# 3_6_1--esp32_-_7-2.net
KiCad netlist of a schematic drawn in EasyEDA Pro
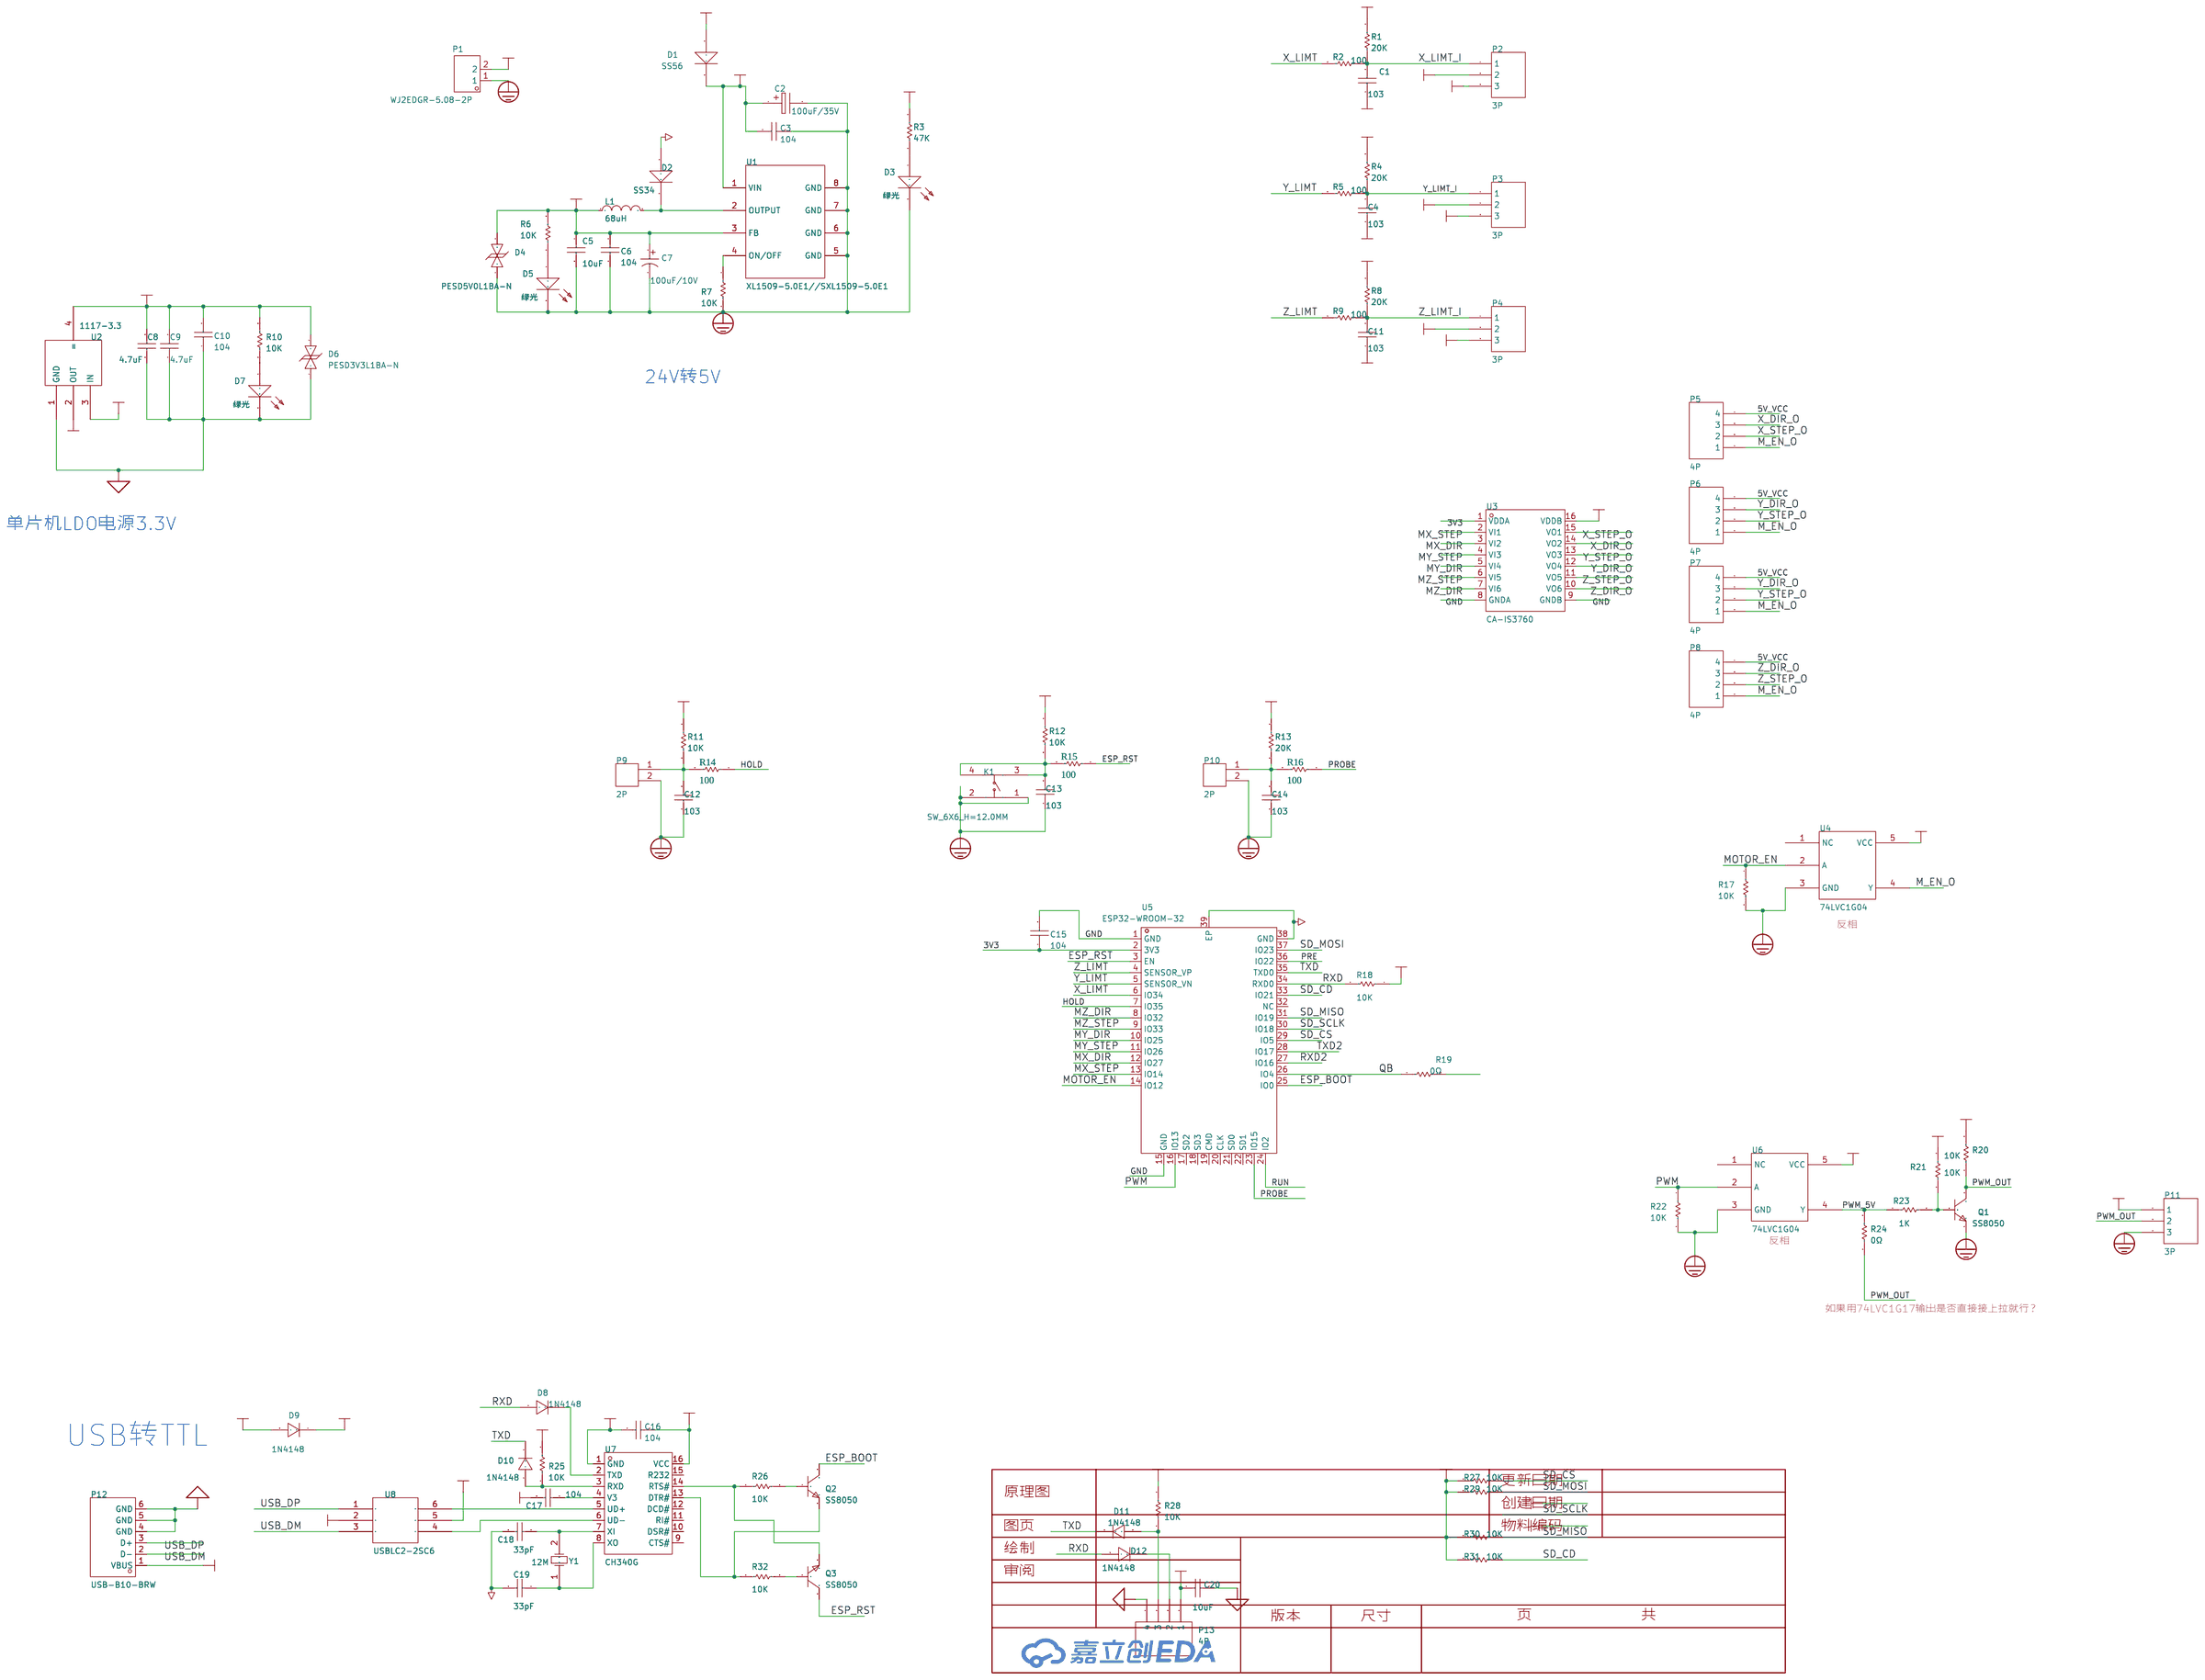
[diagram p0: schematic sheet]

(export (version "E")
  (design (tool "Eeschema 10.0.6"))
  (components
    (comp (ref "C1") (value "103") (footprint "easyedapro:11") (libsource (lib "easyedapro") (part "CAP")))
    (comp (ref "C2")
      (value "100uF/35V")
      (footprint "easyedapro:电解电容贴片10x10")
      (libsource (lib "easyedapro") (part "ELECTRO1"))
    )
    (comp (ref "C3")
      (value "104")
      (footprint "easyedapro:0603C")
      (description "Capacitor (Semiconductor SIM Model)")
      (libsource (lib "easyedapro") (part "Cap Semi"))
    )
    (comp (ref "C4") (value "103") (footprint "easyedapro:11") (libsource (lib "easyedapro") (part "CAP")))
    (comp (ref "C5") (value "10uF") (libsource (lib "") (part "CAP_1")))
    (comp (ref "C6")
      (value "104")
      (footprint "easyedapro:0603C")
      (description "Capacitor (Semiconductor SIM Model)")
      (libsource (lib "easyedapro") (part "Cap Semi"))
    )
    (comp (ref "C7")
      (value "100uF/10V")
      (footprint "easyedapro:CAP-SMD_BD5.0-L5.3-W5.3-RD")
      (fields (field (name "Manufacturer Part") "CS1A101M-CRD54") (field (name "Manufacturer") "ST(先科)"))
      (libsource (lib "easyedapro") (part "CS1A101M-CRD54"))
    )
    (comp (ref "C8") (value "4.7uF") (libsource (lib "") (part "CAP_1")))
    (comp (ref "C9") (value "4.7uF") (libsource (lib "") (part "CAP_1")))
    (comp (ref "C10")
      (value "104")
      (footprint "easyedapro:0603C")
      (description "Capacitor (Semiconductor SIM Model)")
      (libsource (lib "easyedapro") (part "Cap Semi"))
    )
    (comp (ref "C11") (value "103") (footprint "easyedapro:11") (libsource (lib "easyedapro") (part "CAP")))
    (comp (ref "C12") (value "103") (footprint "easyedapro:11") (libsource (lib "easyedapro") (part "CAP")))
    (comp (ref "C13") (value "103") (footprint "easyedapro:11") (libsource (lib "easyedapro") (part "CAP")))
    (comp (ref "C14") (value "103") (footprint "easyedapro:11") (libsource (lib "easyedapro") (part "CAP")))
    (comp (ref "C15")
      (value "104")
      (footprint "easyedapro:0603C")
      (description "Capacitor (Semiconductor SIM Model)")
      (libsource (lib "easyedapro") (part "Cap Semi"))
    )
    (comp (ref "C16")
      (value "104")
      (footprint "easyedapro:0603C")
      (description "Capacitor (Semiconductor SIM Model)")
      (libsource (lib "easyedapro") (part "Cap Semi"))
    )
    (comp (ref "C17")
      (value "104")
      (footprint "easyedapro:0603C")
      (description "Capacitor (Semiconductor SIM Model)")
      (libsource (lib "easyedapro") (part "Cap Semi"))
    )
    (comp (ref "C18")
      (value "18pF")
      (footprint "easyedapro:0603C")
      (description "Capacitor (Semiconductor SIM Model)")
      (libsource (lib "easyedapro") (part "Cap Semi"))
    )
    (comp (ref "C19")
      (value "18pF")
      (footprint "easyedapro:0603C")
      (description "Capacitor (Semiconductor SIM Model)")
      (libsource (lib "easyedapro") (part "Cap Semi"))
    )
    (comp (ref "C20") (value "10uF") (libsource (lib "") (part "CAP_1")))
    (comp (ref "D1") (value "SS56") (footprint "easyedapro:SMA") (libsource (lib "") (part "1N4148_1")))
    (comp (ref "D2") (value "SS34") (libsource (lib "easyedapro") (part "1N4148")))
    (comp (ref "D3")
      (value "绿光")
      (footprint "easyedapro:0603LED")
      (libsource (lib "easyedapro") (part "LED"))
    )
    (comp (ref "D4")
      (value "PESD5V0L1BA-N")
      (footprint "easyedapro:SOD-523_L1.2-W0.8-LS1.6-BI")
      (description "极性:Bidirectional;反向关断电压（典型值）:5V (Max);击穿电压（最小值）:6V;箝位电压:15V;峰值脉冲电流（10/1000us）:5A (8/20us);")
      (fields (field (name "Manufacturer") "BORN伯恩半导体"))
      (libsource (lib "easyedapro") (part "PESD5V0S1BBN"))
    )
    (comp (ref "D5")
      (value "绿光")
      (footprint "easyedapro:0603LED")
      (libsource (lib "easyedapro") (part "LED"))
    )
    (comp (ref "D6")
      (value "PESD3V3L1BA-N")
      (footprint "easyedapro:SOD-523_L1.2-W0.8-LS1.6-BI")
      (description "极性:Bidirectional;反向关断电压（典型值）:5V (Max);击穿电压（最小值）:6V;箝位电压:15V;峰值脉冲电流（10/1000us）:5A (8/20us);")
      (fields (field (name "Manufacturer") "BORN伯恩半导体"))
      (libsource (lib "easyedapro") (part "PESD5V0S1BBN"))
    )
    (comp (ref "D7")
      (value "绿光")
      (footprint "easyedapro:0603LED")
      (libsource (lib "easyedapro") (part "LED"))
    )
    (comp (ref "D8")
      (value "1N4148")
      (footprint "easyedapro:SOD-123_L2.8-W1.8-LS3.7-RD")
      (fields (field (name "Manufacturer") "MCC(美微科)"))
      (libsource (lib "easyedapro") (part "1N4148W-TP"))
    )
    (comp (ref "D9")
      (value "1N4148")
      (footprint "easyedapro:SOD-123_L2.8-W1.8-LS3.7-RD")
      (fields (field (name "Manufacturer") "MCC(美微科)"))
      (libsource (lib "easyedapro") (part "1N4148W-TP"))
    )
    (comp (ref "D10")
      (value "1N4148")
      (footprint "easyedapro:SOD-123_L2.8-W1.8-LS3.7-RD")
      (fields (field (name "Manufacturer") "MCC(美微科)"))
      (libsource (lib "easyedapro") (part "1N4148W-TP"))
    )
    (comp (ref "D11")
      (value "1N4148")
      (footprint "easyedapro:SOD-123_L2.8-W1.8-LS3.7-RD")
      (fields (field (name "Manufacturer") "MCC(美微科)"))
      (libsource (lib "easyedapro") (part "1N4148W-TP"))
    )
    (comp (ref "D12")
      (value "1N4148")
      (footprint "easyedapro:SOD-123_L2.8-W1.8-LS3.7-RD")
      (fields (field (name "Manufacturer") "MCC(美微科)"))
      (libsource (lib "easyedapro") (part "1N4148W-TP"))
    )
    (comp (ref "K1")
      (value "SW_6X6_H=12.0MM")
      (footprint "easyedapro:KEY-SMD_4P-L6.0-W6.0-P4.50-LS9.0")
      (libsource (lib "easyedapro") (part "SW_6X6_H=12.0MM"))
    )
    (comp (ref "L1")
      (value "68uH")
      (footprint "easyedapro:IND-SMD_L7.0-W7.0_SMDRI74-330MT")
      (description "电感值:33uH;精度:±20%;额定电流:960mA;饱和电流(Isat):1.8A;类型:屏蔽电感;")
      (fields (field (name "Manufacturer Part") "SMDRI74-330MT") (field (name "Manufacturer") "SXN(顺翔诺)"))
      (libsource (lib "easyedapro") (part "SMDRI74-330MT"))
    )
    (comp (ref "P1")
      (value "WJ2EDGR-5.08-2P")
      (footprint "easyedapro:CONN-TH_WJ2EDGR-5.08-2P")
      (description "每排PIN数:2;安装方式:弯针;排数:1;间距:5.08mm;连接器类型:板端/插座-开口;")
      (fields (field (name "Manufacturer") "KANGNEX(康奈克斯电气)"))
      (libsource (lib "easyedapro") (part "WJ2EDGR-5.08-2P"))
    )
    (comp (ref "P2")
      (value "3P")
      (footprint "easyedapro:HDR1X3_CON")
      (libsource (lib "easyedapro") (part "3P"))
    )
    (comp (ref "P3")
      (value "3P")
      (footprint "easyedapro:HDR1X3_CON")
      (libsource (lib "easyedapro") (part "3P"))
    )
    (comp (ref "P4")
      (value "3P")
      (footprint "easyedapro:HDR1X3_CON")
      (libsource (lib "easyedapro") (part "3P"))
    )
    (comp (ref "P5")
      (value "4P")
      (footprint "easyedapro:HDR1X4_CON")
      (libsource (lib "easyedapro") (part "4P"))
    )
    (comp (ref "P6")
      (value "4P")
      (footprint "easyedapro:HDR1X4_CON")
      (libsource (lib "easyedapro") (part "4P"))
    )
    (comp (ref "P7")
      (value "4P")
      (footprint "easyedapro:HDR1X4_CON")
      (libsource (lib "easyedapro") (part "4P"))
    )
    (comp (ref "P8")
      (value "4P")
      (footprint "easyedapro:HDR1X4_CON")
      (libsource (lib "easyedapro") (part "4P"))
    )
    (comp (ref "P9") (value "2P") (libsource (lib "easyedapro") (part "2P")))
    (comp (ref "P10") (value "2P") (libsource (lib "easyedapro") (part "2P")))
    (comp (ref "P11")
      (value "3P")
      (footprint "easyedapro:HDR1X3_CON")
      (libsource (lib "easyedapro") (part "3P"))
    )
    (comp (ref "P12")
      (value "USB-B10-BRW")
      (footprint "easyedapro:USB-B-TH_USB-B10-BRW")
      (fields (field (name "Manufacturer") "XUNPU(讯普)"))
      (libsource (lib "easyedapro") (part "USB-B10-BRW"))
    )
    (comp (ref "P13")
      (value "4P")
      (footprint "easyedapro:HDR1X4_CON")
      (libsource (lib "easyedapro") (part "4P"))
    )
    (comp (ref "Q1")
      (value "SS8050")
      (footprint "easyedapro:SOT-23-3_L2.9-W1.3-P1.90-LS2.4-BR")
      (fields (field (name "Manufacturer") "CJ（江苏长电/长晶）"))
      (libsource (lib "easyedapro") (part "SS8050_C2150"))
    )
    (comp (ref "Q2")
      (value "SS8050")
      (footprint "easyedapro:SOT-23-3_L2.9-W1.3-P1.90-LS2.4-BR")
      (fields (field (name "Manufacturer") "Doeshare(德芯)"))
      (libsource (lib "easyedapro") (part "SS8050_C2931717"))
    )
    (comp (ref "Q3")
      (value "SS8050")
      (footprint "easyedapro:SOT-23-3_L2.9-W1.3-P1.90-LS2.4-BR")
      (fields (field (name "Manufacturer") "Doeshare(德芯)"))
      (libsource (lib "easyedapro") (part "SS8050_C2931717"))
    )
    (comp (ref "R1")
      (value "20K")
      (footprint "easyedapro:10")
      (description "Resistor")
      (libsource (lib "easyedapro") (part "RES"))
    )
    (comp (ref "R2")
      (value "100")
      (footprint "easyedapro:10")
      (description "Resistor")
      (libsource (lib "easyedapro") (part "RES"))
    )
    (comp (ref "R3")
      (value "47K")
      (footprint "easyedapro:0603R")
      (description "Resistor")
      (libsource (lib "easyedapro") (part "RES"))
    )
    (comp (ref "R4")
      (value "20K")
      (footprint "easyedapro:10")
      (description "Resistor")
      (libsource (lib "easyedapro") (part "RES"))
    )
    (comp (ref "R5")
      (value "100")
      (footprint "easyedapro:10")
      (description "Resistor")
      (libsource (lib "easyedapro") (part "RES"))
    )
    (comp (ref "R6")
      (value "10K")
      (footprint "easyedapro:0603R")
      (description "Resistor")
      (libsource (lib "easyedapro") (part "RES"))
    )
    (comp (ref "R7")
      (value "10K")
      (footprint "easyedapro:0603R")
      (description "Resistor")
      (libsource (lib "easyedapro") (part "RES"))
    )
    (comp (ref "R8")
      (value "20K")
      (footprint "easyedapro:10")
      (description "Resistor")
      (libsource (lib "easyedapro") (part "RES"))
    )
    (comp (ref "R9")
      (value "100")
      (footprint "easyedapro:10")
      (description "Resistor")
      (libsource (lib "easyedapro") (part "RES"))
    )
    (comp (ref "R10")
      (value "10K")
      (footprint "easyedapro:0603R")
      (description "Resistor")
      (libsource (lib "easyedapro") (part "RES"))
    )
    (comp (ref "R11")
      (value "10K")
      (footprint "easyedapro:0603R")
      (description "Resistor")
      (libsource (lib "easyedapro") (part "RES"))
    )
    (comp (ref "R12")
      (value "10K")
      (footprint "easyedapro:0603R")
      (description "Resistor")
      (libsource (lib "easyedapro") (part "RES"))
    )
    (comp (ref "R13")
      (value "10K")
      (footprint "easyedapro:0603R")
      (description "Resistor")
      (libsource (lib "easyedapro") (part "RES"))
    )
    (comp (ref "R14")
      (value "100")
      (description "Resistor")
      (fields (field (name "Publisher") "Altium Limited"))
      (libsource (lib "") (part "RES_1"))
    )
    (comp (ref "R15")
      (value "100")
      (description "Resistor")
      (fields (field (name "Publisher") "Altium Limited"))
      (libsource (lib "") (part "RES_1"))
    )
    (comp (ref "R16")
      (value "100")
      (description "Resistor")
      (fields (field (name "Publisher") "Altium Limited"))
      (libsource (lib "") (part "RES_1"))
    )
    (comp (ref "R17")
      (value "10K")
      (description "Resistor")
      (fields (field (name "Publisher") "Altium Limited"))
      (libsource (lib "") (part "RES_1"))
    )
    (comp (ref "R18")
      (value "10K")
      (footprint "easyedapro:0603R")
      (description "Resistor")
      (libsource (lib "easyedapro") (part "RES"))
    )
    (comp (ref "R19")
      (value "0Ω")
      (description "Resistor")
      (fields (field (name "Publisher") "Altium Limited"))
      (libsource (lib "") (part "RES_1"))
    )
    (comp (ref "R20")
      (value "10K")
      (description "Resistor")
      (fields (field (name "Publisher") "Altium Limited"))
      (libsource (lib "") (part "RES_1"))
    )
    (comp (ref "R21")
      (value "10K")
      (description "Resistor")
      (fields (field (name "Publisher") "Altium Limited"))
      (libsource (lib "") (part "RES_1"))
    )
    (comp (ref "R22")
      (value "10K")
      (description "Resistor")
      (fields (field (name "Publisher") "Altium Limited"))
      (libsource (lib "") (part "RES_1"))
    )
    (comp (ref "R23")
      (value "1K")
      (description "Resistor")
      (fields (field (name "Publisher") "Altium Limited"))
      (libsource (lib "") (part "RES_1"))
    )
    (comp (ref "R24")
      (value "0Ω")
      (description "Resistor")
      (fields (field (name "Publisher") "Altium Limited"))
      (libsource (lib "") (part "RES_1"))
    )
    (comp (ref "R25")
      (value "10K")
      (footprint "easyedapro:0603R")
      (description "Resistor")
      (libsource (lib "easyedapro") (part "RES"))
    )
    (comp (ref "R26")
      (value "10K")
      (footprint "easyedapro:0603R")
      (description "Resistor")
      (libsource (lib "easyedapro") (part "RES"))
    )
    (comp (ref "R27")
      (value "10K")
      (footprint "easyedapro:10")
      (description "Resistor")
      (libsource (lib "easyedapro") (part "RES"))
    )
    (comp (ref "R28")
      (value "10K")
      (footprint "easyedapro:0603R")
      (description "Resistor")
      (libsource (lib "easyedapro") (part "RES"))
    )
    (comp (ref "R29")
      (value "10K")
      (footprint "easyedapro:10")
      (description "Resistor")
      (libsource (lib "easyedapro") (part "RES"))
    )
    (comp (ref "R30")
      (value "10K")
      (footprint "easyedapro:10")
      (description "Resistor")
      (libsource (lib "easyedapro") (part "RES"))
    )
    (comp (ref "R31")
      (value "10K")
      (footprint "easyedapro:10")
      (description "Resistor")
      (libsource (lib "easyedapro") (part "RES"))
    )
    (comp (ref "R32")
      (value "10K")
      (footprint "easyedapro:0603R")
      (description "Resistor")
      (libsource (lib "easyedapro") (part "RES"))
    )
    (comp (ref "U1")
      (value "XL1509-5.0E1//SXL1509-5.0E1")
      (footprint "easyedapro:SOIC-8_L5.0-W4.0-P1.27-LS6.0-BL")
      (description "功能类型:降压型;同步整流:-;输出通道数:-;拓扑结构:-;输入电压:-;输出电流(最大值):-;开关频率:-;")
      (fields (field (name "Manufacturer") "XLSEMI(芯龙)"))
      (libsource (lib "easyedapro") (part "XL1509-5.0E1"))
    )
    (comp (ref "U2")
      (value "1117-3.3")
      (footprint "easyedapro:SOT-223")
      (libsource (lib "easyedapro") (part "LM1117"))
    )
    (comp (ref "U3")
      (value "CA-IS3760")
      (footprint "easyedapro:SOIC-16_L9.9-W3.9-P1.27-LS6.0-BL")
      (fields (field (name "Manufacturer") "Chipanalog(川土微)"))
      (libsource (lib "easyedapro") (part "CA-IS3760HN"))
    )
    (comp (ref "U4")
      (value "74LVC1G04")
      (footprint "easyedapro:SMD8")
      (libsource (lib "easyedapro") (part "74LVC1G04"))
    )
    (comp (ref "U5")
      (value "ESP32-WROOM-32")
      (footprint "easyedapro:WIFIM-SMD_ESP-WROOM-32")
      (description "WiFi+双模蓝牙 双核CPU 网口 顶配MCU 低功耗蓝牙 ESP32系列ESP-WROOM-32模组/ESP-32S 4MB")
      (fields (field (name "Manufacturer") "ESPRESSIF(乐鑫)"))
      (libsource (lib "easyedapro") (part "ESP-WROOM-32"))
    )
    (comp (ref "U6")
      (value "74LVC1G04")
      (footprint "easyedapro:SMD8")
      (libsource (lib "easyedapro") (part "74LVC1G04"))
    )
    (comp (ref "U7")
      (value "CH340G")
      (footprint "easyedapro:SOIC-16_L9.9-W3.9-P1.27-LS6.0-BL")
      (description "应用功能:收发器;接口协议:USB 2.0;数据速率:2Mbps;")
      (fields (field (name "Manufacturer") "WCH(南京沁恒)"))
      (libsource (lib "easyedapro") (part "CH340G"))
    )
    (comp (ref "U8")
      (value "USBLC2-2SC6")
      (footprint "easyedapro:SOT-23-6")
      (libsource (lib "easyedapro") (part "DIP6"))
    )
    (comp (ref "Y1")
      (value "12M")
      (footprint "easyedapro:晶振贴片49SSMD")
      (description "Crystal Oscillator")
      (libsource (lib "easyedapro") (part "XTAL"))
    )
  )
  (nets
    (net (code "1") (name "/ESP_BOOT") (class "Default")
      (node (ref "Q2") (pin "3") (pinfunction "C_3") (pintype "unspecified"))
      (node (ref "U5") (pin "25") (pinfunction "IO0_25") (pintype "unspecified"))
    )
    (net (code "2") (name "/ESP_RST") (class "Default")
      (node (ref "Q3") (pin "3") (pinfunction "C_3") (pintype "unspecified"))
      (node (ref "R15") (pin "1") (pinfunction "1_1") (pintype "input"))
      (node (ref "U5") (pin "3") (pinfunction "EN_3") (pintype "unspecified"))
    )
    (net (code "3") (name "/HOLD") (class "Default")
      (node (ref "R14") (pin "1") (pinfunction "1_1") (pintype "input"))
      (node (ref "U5") (pin "7") (pinfunction "IO35_7") (pintype "unspecified"))
    )
    (net (code "4") (name "/MOTOR_EN") (class "Default")
      (node (ref "R17") (pin "1") (pinfunction "1_1") (pintype "input"))
      (node (ref "U4") (pin "2") (pinfunction "A_2") (pintype "unspecified"))
      (node (ref "U5") (pin "14") (pinfunction "IO12_14") (pintype "unspecified"))
    )
    (net (code "5") (name "/MX_DIR") (class "Default")
      (node (ref "U3") (pin "3") (pinfunction "VI2_3") (pintype "unspecified"))
      (node (ref "U5") (pin "12") (pinfunction "IO27_12") (pintype "unspecified"))
    )
    (net (code "6") (name "/MX_STEP") (class "Default")
      (node (ref "U3") (pin "2") (pinfunction "VI1_2") (pintype "unspecified"))
      (node (ref "U5") (pin "13") (pinfunction "IO14_13") (pintype "unspecified"))
    )
    (net (code "7") (name "/MY_DIR") (class "Default")
      (node (ref "U3") (pin "5") (pinfunction "VI4_5") (pintype "unspecified"))
      (node (ref "U5") (pin "10") (pinfunction "IO25_10") (pintype "unspecified"))
    )
    (net (code "8") (name "/MY_STEP") (class "Default")
      (node (ref "U3") (pin "4") (pinfunction "VI3_4") (pintype "unspecified"))
      (node (ref "U5") (pin "11") (pinfunction "IO26_11") (pintype "unspecified"))
    )
    (net (code "9") (name "/MZ_DIR") (class "Default")
      (node (ref "U3") (pin "7") (pinfunction "VI6_7") (pintype "unspecified"))
      (node (ref "U5") (pin "8") (pinfunction "IO32_8") (pintype "unspecified"))
    )
    (net (code "10") (name "/MZ_STEP") (class "Default")
      (node (ref "U3") (pin "6") (pinfunction "VI5_6") (pintype "unspecified"))
      (node (ref "U5") (pin "9") (pinfunction "IO33_9") (pintype "unspecified"))
    )
    (net (code "11") (name "/M_EN_O") (class "Default")
      (node (ref "P5") (pin "1") (pinfunction "1_1") (pintype "unspecified"))
      (node (ref "P6") (pin "1") (pinfunction "1_1") (pintype "unspecified"))
      (node (ref "P7") (pin "1") (pinfunction "1_1") (pintype "unspecified"))
      (node (ref "P8") (pin "1") (pinfunction "1_1") (pintype "unspecified"))
      (node (ref "U4") (pin "4") (pinfunction "Y_4") (pintype "unspecified"))
    )
    (net (code "12") (name "/PRE") (class "Default")
      (node (ref "U5") (pin "36") (pinfunction "IO22_36") (pintype "unspecified"))
    )
    (net (code "13") (name "/PROBE") (class "Default")
      (node (ref "R16") (pin "1") (pinfunction "1_1") (pintype "input"))
      (node (ref "U5") (pin "23") (pinfunction "IO15_23") (pintype "unspecified"))
    )
    (net (code "14") (name "/PWM") (class "Default")
      (node (ref "R22") (pin "1") (pinfunction "1_1") (pintype "input"))
      (node (ref "U5") (pin "16") (pinfunction "IO13_16") (pintype "unspecified"))
      (node (ref "U6") (pin "2") (pinfunction "A_2") (pintype "unspecified"))
    )
    (net (code "15") (name "/PWM_5V") (class "Default")
      (node (ref "R23") (pin "1") (pinfunction "1_1") (pintype "input"))
      (node (ref "R24") (pin "2") (pinfunction "2_2") (pintype "input"))
      (node (ref "U6") (pin "4") (pinfunction "Y_4") (pintype "unspecified"))
    )
    (net (code "16") (name "/PWM_OUT") (class "Default")
      (node (ref "P11") (pin "2") (pinfunction "2_2") (pintype "unspecified"))
      (node (ref "Q1") (pin "3") (pinfunction "C_3") (pintype "input"))
      (node (ref "R20") (pin "1") (pinfunction "1_1") (pintype "input"))
      (node (ref "R24") (pin "1") (pinfunction "1_1") (pintype "input"))
    )
    (net (code "17") (name "/QB") (class "Default")
      (node (ref "R19") (pin "1") (pinfunction "1_1") (pintype "input"))
      (node (ref "U5") (pin "26") (pinfunction "IO4_26") (pintype "unspecified"))
    )
    (net (code "18") (name "/RUN") (class "Default")
      (node (ref "U5") (pin "24") (pinfunction "IO2_24") (pintype "unspecified"))
    )
    (net (code "19") (name "/RXD") (class "Default")
      (node (ref "D12") (pin "2") (pinfunction "A_2") (pintype "input"))
      (node (ref "D8") (pin "2") (pinfunction "A_2") (pintype "input"))
      (node (ref "R18") (pin "2") (pinfunction "2_2") (pintype "unspecified"))
      (node (ref "U5") (pin "34") (pinfunction "RXD0_34") (pintype "unspecified"))
    )
    (net (code "20") (name "/RXD2") (class "Default")
      (node (ref "U5") (pin "27") (pinfunction "IO16_27") (pintype "unspecified"))
    )
    (net (code "21") (name "/SD_CD") (class "Default")
      (node (ref "R31") (pin "1") (pinfunction "1_1") (pintype "unspecified"))
      (node (ref "U5") (pin "33") (pinfunction "IO21_33") (pintype "unspecified"))
    )
    (net (code "22") (name "/SD_CS") (class "Default")
      (node (ref "R27") (pin "1") (pinfunction "1_1") (pintype "unspecified"))
      (node (ref "U5") (pin "29") (pinfunction "IO5_29") (pintype "unspecified"))
    )
    (net (code "23") (name "/SD_MISO") (class "Default")
      (node (ref "R30") (pin "1") (pinfunction "1_1") (pintype "unspecified"))
      (node (ref "U5") (pin "31") (pinfunction "IO19_31") (pintype "unspecified"))
    )
    (net (code "24") (name "/SD_MOSI") (class "Default")
      (node (ref "R29") (pin "1") (pinfunction "1_1") (pintype "unspecified"))
      (node (ref "U5") (pin "37") (pinfunction "IO23_37") (pintype "unspecified"))
    )
    (net (code "25") (name "/SD_SCLK") (class "Default")
      (node (ref "U5") (pin "30") (pinfunction "IO18_30") (pintype "unspecified"))
    )
    (net (code "26") (name "/TXD") (class "Default")
      (node (ref "D10") (pin "1") (pinfunction "c_1") (pintype "input"))
      (node (ref "D11") (pin "1") (pinfunction "c_1") (pintype "input"))
      (node (ref "U5") (pin "35") (pinfunction "TXD0_35") (pintype "unspecified"))
    )
    (net (code "27") (name "/TXD2") (class "Default")
      (node (ref "U5") (pin "28") (pinfunction "IO17_28") (pintype "unspecified"))
    )
    (net (code "28") (name "/USB_DM") (class "Default")
      (node (ref "P12") (pin "2") (pinfunction "D-_2") (pintype "unspecified"))
      (node (ref "U8") (pin "3") (pinfunction "3_3") (pintype "unspecified"))
    )
    (net (code "29") (name "/USB_DP") (class "Default")
      (node (ref "P12") (pin "3") (pinfunction "D+_3") (pintype "unspecified"))
      (node (ref "U8") (pin "1") (pinfunction "1_1") (pintype "unspecified"))
    )
    (net (code "30") (name "/X_DIR_O") (class "Default")
      (node (ref "P5") (pin "3") (pinfunction "3_3") (pintype "unspecified"))
      (node (ref "U3") (pin "14") (pinfunction "VO2_14") (pintype "unspecified"))
    )
    (net (code "31") (name "/X_LIMT") (class "Default")
      (node (ref "R2") (pin "2") (pinfunction "2_2") (pintype "unspecified"))
      (node (ref "U5") (pin "6") (pinfunction "IO34_6") (pintype "unspecified"))
    )
    (net (code "32") (name "/X_LIMT_I") (class "Default")
      (node (ref "C1") (pin "2") (pinfunction "2_2") (pintype "unspecified"))
      (node (ref "P2") (pin "1") (pinfunction "1_1") (pintype "unspecified"))
      (node (ref "R1") (pin "1") (pinfunction "1_1") (pintype "unspecified"))
      (node (ref "R2") (pin "1") (pinfunction "1_1") (pintype "unspecified"))
    )
    (net (code "33") (name "/X_STEP_O") (class "Default")
      (node (ref "P5") (pin "2") (pinfunction "2_2") (pintype "unspecified"))
      (node (ref "U3") (pin "15") (pinfunction "VO1_15") (pintype "unspecified"))
    )
    (net (code "34") (name "/Y_DIR_O") (class "Default")
      (node (ref "P6") (pin "3") (pinfunction "3_3") (pintype "unspecified"))
      (node (ref "P7") (pin "3") (pinfunction "3_3") (pintype "unspecified"))
      (node (ref "U3") (pin "12") (pinfunction "VO4_12") (pintype "unspecified"))
    )
    (net (code "35") (name "/Y_LIMT") (class "Default")
      (node (ref "R5") (pin "2") (pinfunction "2_2") (pintype "unspecified"))
      (node (ref "U5") (pin "5") (pinfunction "SENSOR_VN_5") (pintype "unspecified"))
    )
    (net (code "36") (name "/Y_LIMT_I") (class "Default")
      (node (ref "C4") (pin "2") (pinfunction "2_2") (pintype "unspecified"))
      (node (ref "P3") (pin "1") (pinfunction "1_1") (pintype "unspecified"))
      (node (ref "R4") (pin "1") (pinfunction "1_1") (pintype "unspecified"))
      (node (ref "R5") (pin "1") (pinfunction "1_1") (pintype "unspecified"))
    )
    (net (code "37") (name "/Y_STEP_O") (class "Default")
      (node (ref "P6") (pin "2") (pinfunction "2_2") (pintype "unspecified"))
      (node (ref "P7") (pin "2") (pinfunction "2_2") (pintype "unspecified"))
      (node (ref "U3") (pin "13") (pinfunction "VO3_13") (pintype "unspecified"))
    )
    (net (code "38") (name "/Z_DIR_O") (class "Default")
      (node (ref "P8") (pin "3") (pinfunction "3_3") (pintype "unspecified"))
      (node (ref "U3") (pin "10") (pinfunction "VO6_10") (pintype "unspecified"))
    )
    (net (code "39") (name "/Z_LIMT") (class "Default")
      (node (ref "R9") (pin "2") (pinfunction "2_2") (pintype "unspecified"))
      (node (ref "U5") (pin "4") (pinfunction "SENSOR_VP_4") (pintype "unspecified"))
    )
    (net (code "40") (name "/Z_LIMT_I") (class "Default")
      (node (ref "C11") (pin "2") (pinfunction "2_2") (pintype "unspecified"))
      (node (ref "P4") (pin "1") (pinfunction "1_1") (pintype "unspecified"))
      (node (ref "R8") (pin "1") (pinfunction "1_1") (pintype "unspecified"))
      (node (ref "R9") (pin "1") (pinfunction "1_1") (pintype "unspecified"))
    )
    (net (code "41") (name "/Z_STEP_O") (class "Default")
      (node (ref "P8") (pin "2") (pinfunction "2_2") (pintype "unspecified"))
      (node (ref "U3") (pin "11") (pinfunction "VO5_11") (pintype "unspecified"))
    )
    (net (code "42") (name "3V3") (class "Default")
      (node (ref "C10") (pin "2") (pinfunction "2_2") (pintype "unspecified"))
      (node (ref "C15") (pin "1") (pinfunction "1_1") (pintype "unspecified"))
      (node (ref "C8") (pin "2") (pinfunction "2_2") (pintype "input"))
      (node (ref "C9") (pin "2") (pinfunction "2_2") (pintype "input"))
      (node (ref "D6") (pin "2") (pinfunction "2_2") (pintype "input"))
      (node (ref "R10") (pin "2") (pinfunction "2_2") (pintype "unspecified"))
      (node (ref "R11") (pin "1") (pinfunction "1_1") (pintype "unspecified"))
      (node (ref "R12") (pin "1") (pinfunction "1_1") (pintype "unspecified"))
      (node (ref "R18") (pin "1") (pinfunction "1_1") (pintype "unspecified"))
      (node (ref "R27") (pin "2") (pinfunction "2_2") (pintype "unspecified"))
      (node (ref "R29") (pin "2") (pinfunction "2_2") (pintype "unspecified"))
      (node (ref "R30") (pin "2") (pinfunction "2_2") (pintype "unspecified"))
      (node (ref "R31") (pin "2") (pinfunction "2_2") (pintype "unspecified"))
      (node (ref "U2") (pin "2") (pinfunction "OUT_2") (pintype "unspecified"))
      (node (ref "U2") (pin "4") (pinfunction "=_4") (pintype "unspecified"))
      (node (ref "U3") (pin "1") (pinfunction "VDDA_1") (pintype "unspecified"))
      (node (ref "U5") (pin "2") (pinfunction "3V3_2") (pintype "unspecified"))
    )
    (net (code "43") (name "5V_VCC") (class "Default")
      (node (ref "C16") (pin "1") (pinfunction "1_1") (pintype "unspecified"))
      (node (ref "C20") (pin "1") (pinfunction "1_1") (pintype "input"))
      (node (ref "C5") (pin "1") (pinfunction "1_1") (pintype "input"))
      (node (ref "C6") (pin "2") (pinfunction "2_2") (pintype "unspecified"))
      (node (ref "C7") (pin "1") (pinfunction "1_1") (pintype "input"))
      (node (ref "D4") (pin "2") (pinfunction "2_2") (pintype "input"))
      (node (ref "D9") (pin "1") (pinfunction "c_1") (pintype "input"))
      (node (ref "L1") (pin "1") (pinfunction "1_1") (pintype "unspecified"))
      (node (ref "P11") (pin "1") (pinfunction "1_1") (pintype "unspecified"))
      (node (ref "P13") (pin "1") (pinfunction "1_1") (pintype "unspecified"))
      (node (ref "P2") (pin "3") (pinfunction "3_3") (pintype "unspecified"))
      (node (ref "P3") (pin "3") (pinfunction "3_3") (pintype "unspecified"))
      (node (ref "P4") (pin "3") (pinfunction "3_3") (pintype "unspecified"))
      (node (ref "P5") (pin "4") (pinfunction "4_4") (pintype "unspecified"))
      (node (ref "P6") (pin "4") (pinfunction "4_4") (pintype "unspecified"))
      (node (ref "P7") (pin "4") (pinfunction "4_4") (pintype "unspecified"))
      (node (ref "P8") (pin "4") (pinfunction "4_4") (pintype "unspecified"))
      (node (ref "R1") (pin "2") (pinfunction "2_2") (pintype "unspecified"))
      (node (ref "R13") (pin "1") (pinfunction "1_1") (pintype "unspecified"))
      (node (ref "R20") (pin "2") (pinfunction "2_2") (pintype "input"))
      (node (ref "R21") (pin "2") (pinfunction "2_2") (pintype "input"))
      (node (ref "R25") (pin "2") (pinfunction "2_2") (pintype "unspecified"))
      (node (ref "R28") (pin "2") (pinfunction "2_2") (pintype "unspecified"))
      (node (ref "R4") (pin "2") (pinfunction "2_2") (pintype "unspecified"))
      (node (ref "R6") (pin "2") (pinfunction "2_2") (pintype "unspecified"))
      (node (ref "R8") (pin "2") (pinfunction "2_2") (pintype "unspecified"))
      (node (ref "U1") (pin "3") (pinfunction "FB_3") (pintype "input"))
      (node (ref "U2") (pin "3") (pinfunction "IN_3") (pintype "unspecified"))
      (node (ref "U3") (pin "16") (pinfunction "VDDB_16") (pintype "unspecified"))
      (node (ref "U4") (pin "5") (pinfunction "VCC_5") (pintype "unspecified"))
      (node (ref "U6") (pin "5") (pinfunction "VCC_5") (pintype "unspecified"))
      (node (ref "U7") (pin "16") (pinfunction "VCC_16") (pintype "unspecified"))
    )
    (net (code "44") (name "24V") (class "Default")
      (node (ref "D1") (pin "1") (pinfunction "1_1") (pintype "unspecified"))
      (node (ref "P1") (pin "2") (pinfunction "2_2") (pintype "input"))
      (node (ref "R3") (pin "2") (pinfunction "2_2") (pintype "unspecified"))
    )
    (net (code "45") (name "GND") (class "Default")
      (node (ref "C1") (pin "1") (pinfunction "1_1") (pintype "unspecified"))
      (node (ref "C10") (pin "1") (pinfunction "1_1") (pintype "unspecified"))
      (node (ref "C11") (pin "1") (pinfunction "1_1") (pintype "unspecified"))
      (node (ref "C12") (pin "1") (pinfunction "1_1") (pintype "unspecified"))
      (node (ref "C13") (pin "1") (pinfunction "1_1") (pintype "unspecified"))
      (node (ref "C14") (pin "1") (pinfunction "1_1") (pintype "unspecified"))
      (node (ref "C15") (pin "2") (pinfunction "2_2") (pintype "unspecified"))
      (node (ref "C16") (pin "2") (pinfunction "2_2") (pintype "unspecified"))
      (node (ref "C17") (pin "2") (pinfunction "2_2") (pintype "unspecified"))
      (node (ref "C18") (pin "2") (pinfunction "2_2") (pintype "unspecified"))
      (node (ref "C19") (pin "2") (pinfunction "2_2") (pintype "unspecified"))
      (node (ref "C2") (pin "2") (pintype "unspecified"))
      (node (ref "C20") (pin "2") (pinfunction "2_2") (pintype "input"))
      (node (ref "C3") (pin "1") (pinfunction "1_1") (pintype "unspecified"))
      (node (ref "C4") (pin "1") (pinfunction "1_1") (pintype "unspecified"))
      (node (ref "C5") (pin "2") (pinfunction "2_2") (pintype "input"))
      (node (ref "C6") (pin "1") (pinfunction "1_1") (pintype "unspecified"))
      (node (ref "C7") (pin "2") (pinfunction "2_2") (pintype "input"))
      (node (ref "C8") (pin "1") (pinfunction "1_1") (pintype "input"))
      (node (ref "C9") (pin "1") (pinfunction "1_1") (pintype "input"))
      (node (ref "D2") (pin "1") (pinfunction "1_1") (pintype "input"))
      (node (ref "D3") (pin "2") (pinfunction "2_2") (pintype "unspecified"))
      (node (ref "D4") (pin "1") (pinfunction "1_1") (pintype "input"))
      (node (ref "D5") (pin "2") (pinfunction "2_2") (pintype "unspecified"))
      (node (ref "D6") (pin "1") (pinfunction "1_1") (pintype "input"))
      (node (ref "D7") (pin "2") (pinfunction "2_2") (pintype "unspecified"))
      (node (ref "K1") (pin "1") (pinfunction "1_1") (pintype "unspecified"))
      (node (ref "K1") (pin "2") (pinfunction "2_2") (pintype "unspecified"))
      (node (ref "P1") (pin "1") (pinfunction "1_1") (pintype "input"))
      (node (ref "P10") (pin "2") (pintype "input"))
      (node (ref "P11") (pin "3") (pinfunction "3_3") (pintype "unspecified"))
      (node (ref "P12") (pin "4") (pinfunction "GND_4") (pintype "unspecified"))
      (node (ref "P12") (pin "5") (pinfunction "GND_5") (pintype "unspecified"))
      (node (ref "P12") (pin "6") (pinfunction "GND_6") (pintype "unspecified"))
      (node (ref "P13") (pin "4") (pinfunction "4_4") (pintype "unspecified"))
      (node (ref "P2") (pin "2") (pinfunction "2_2") (pintype "unspecified"))
      (node (ref "P3") (pin "2") (pinfunction "2_2") (pintype "unspecified"))
      (node (ref "P4") (pin "2") (pinfunction "2_2") (pintype "unspecified"))
      (node (ref "P9") (pin "2") (pintype "input"))
      (node (ref "Q1") (pin "2") (pinfunction "E_2") (pintype "input"))
      (node (ref "R17") (pin "2") (pinfunction "2_2") (pintype "input"))
      (node (ref "R22") (pin "2") (pinfunction "2_2") (pintype "input"))
      (node (ref "R7") (pin "2") (pinfunction "2_2") (pintype "unspecified"))
      (node (ref "U1") (pin "5") (pinfunction "GND_5") (pintype "input"))
      (node (ref "U1") (pin "6") (pinfunction "GND_6") (pintype "input"))
      (node (ref "U1") (pin "7") (pinfunction "GND_7") (pintype "input"))
      (node (ref "U1") (pin "8") (pinfunction "GND_8") (pintype "input"))
      (node (ref "U2") (pin "1") (pinfunction "GND_1") (pintype "unspecified"))
      (node (ref "U3") (pin "8") (pinfunction "GNDA_8") (pintype "unspecified"))
      (node (ref "U3") (pin "9") (pinfunction "GNDB_9") (pintype "unspecified"))
      (node (ref "U4") (pin "3") (pinfunction "GND_3") (pintype "unspecified"))
      (node (ref "U5") (pin "1") (pinfunction "GND_1") (pintype "unspecified"))
      (node (ref "U5") (pin "15") (pinfunction "GND_15") (pintype "unspecified"))
      (node (ref "U5") (pin "38") (pinfunction "GND_38") (pintype "unspecified"))
      (node (ref "U5") (pin "39") (pinfunction "EP_39") (pintype "unspecified"))
      (node (ref "U6") (pin "3") (pinfunction "GND_3") (pintype "unspecified"))
      (node (ref "U7") (pin "1") (pinfunction "GND_1") (pintype "unspecified"))
      (node (ref "U8") (pin "2") (pinfunction "2_2") (pintype "unspecified"))
    )
    (net (code "46") (name "Net-(C12-Pad2)") (class "Default")
      (node (ref "C12") (pin "2") (pinfunction "2_2") (pintype "unspecified"))
      (node (ref "P9") (pin "1") (pintype "input"))
      (node (ref "R11") (pin "2") (pinfunction "2_2") (pintype "unspecified"))
      (node (ref "R14") (pin "2") (pinfunction "2_2") (pintype "input"))
    )
    (net (code "47") (name "Net-(C13-Pad2)") (class "Default")
      (node (ref "C13") (pin "2") (pinfunction "2_2") (pintype "unspecified"))
      (node (ref "K1") (pin "3") (pinfunction "3_3") (pintype "unspecified"))
      (node (ref "K1") (pin "4") (pinfunction "4_4") (pintype "unspecified"))
      (node (ref "R12") (pin "2") (pinfunction "2_2") (pintype "unspecified"))
      (node (ref "R15") (pin "2") (pinfunction "2_2") (pintype "input"))
    )
    (net (code "48") (name "Net-(C14-Pad2)") (class "Default")
      (node (ref "C14") (pin "2") (pinfunction "2_2") (pintype "unspecified"))
      (node (ref "P10") (pin "1") (pintype "input"))
      (node (ref "R13") (pin "2") (pinfunction "2_2") (pintype "unspecified"))
      (node (ref "R16") (pin "2") (pinfunction "2_2") (pintype "input"))
    )
    (net (code "49") (name "Net-(D3-Pad1)") (class "Default")
      (node (ref "D3") (pin "1") (pinfunction "1_1") (pintype "unspecified"))
      (node (ref "R3") (pin "1") (pinfunction "1_1") (pintype "unspecified"))
    )
    (net (code "50") (name "Net-(D5-Pad1)") (class "Default")
      (node (ref "D5") (pin "1") (pinfunction "1_1") (pintype "unspecified"))
      (node (ref "R6") (pin "1") (pinfunction "1_1") (pintype "unspecified"))
    )
    (net (code "51") (name "Net-(D7-Pad1)") (class "Default")
      (node (ref "D7") (pin "1") (pinfunction "1_1") (pintype "unspecified"))
      (node (ref "R10") (pin "1") (pinfunction "1_1") (pintype "unspecified"))
    )
    (net (code "52") (name "Net-(D8-c)") (class "Default")
      (node (ref "D8") (pin "1") (pinfunction "c_1") (pintype "input"))
      (node (ref "U7") (pin "2") (pinfunction "TXD_2") (pintype "unspecified"))
    )
    (net (code "53") (name "Net-(D10-A)") (class "Default")
      (node (ref "D10") (pin "2") (pinfunction "A_2") (pintype "input"))
      (node (ref "R25") (pin "1") (pinfunction "1_1") (pintype "unspecified"))
      (node (ref "U7") (pin "3") (pinfunction "RXD_3") (pintype "unspecified"))
    )
    (net (code "54") (name "Net-(D11-A)") (class "Default")
      (node (ref "D11") (pin "2") (pinfunction "A_2") (pintype "input"))
      (node (ref "P13") (pin "3") (pinfunction "3_3") (pintype "unspecified"))
      (node (ref "R28") (pin "1") (pinfunction "1_1") (pintype "unspecified"))
    )
    (net (code "55") (name "Net-(D12-c)") (class "Default")
      (node (ref "D12") (pin "1") (pinfunction "c_1") (pintype "input"))
      (node (ref "P13") (pin "2") (pinfunction "2_2") (pintype "unspecified"))
    )
    (net (code "56") (name "Net-(Q1-B)") (class "Default")
      (node (ref "Q1") (pin "1") (pinfunction "B_1") (pintype "input"))
      (node (ref "R21") (pin "1") (pinfunction "1_1") (pintype "input"))
      (node (ref "R23") (pin "2") (pinfunction "2_2") (pintype "input"))
    )
    (net (code "57") (name "Net-(Q2-B)") (class "Default")
      (node (ref "Q2") (pin "1") (pinfunction "B_1") (pintype "unspecified"))
      (node (ref "R26") (pin "2") (pinfunction "2_2") (pintype "unspecified"))
    )
    (net (code "58") (name "Net-(Q2-E)") (class "Default")
      (node (ref "Q2") (pin "2") (pinfunction "E_2") (pintype "unspecified"))
      (node (ref "R32") (pin "1") (pinfunction "1_1") (pintype "unspecified"))
      (node (ref "U7") (pin "13") (pinfunction "DTR#_13") (pintype "unspecified"))
    )
    (net (code "59") (name "Net-(Q3-B)") (class "Default")
      (node (ref "Q3") (pin "1") (pinfunction "B_1") (pintype "unspecified"))
      (node (ref "R32") (pin "2") (pinfunction "2_2") (pintype "unspecified"))
    )
    (net (code "60") (name "Net-(Q3-E)") (class "Default")
      (node (ref "Q3") (pin "2") (pinfunction "E_2") (pintype "unspecified"))
      (node (ref "R26") (pin "1") (pinfunction "1_1") (pintype "unspecified"))
      (node (ref "U7") (pin "14") (pinfunction "RTS#_14") (pintype "unspecified"))
    )
    (net (code "61") (name "Net-(U1-ON{slash}OFF)") (class "Default")
      (node (ref "R7") (pin "1") (pinfunction "1_1") (pintype "unspecified"))
      (node (ref "U1") (pin "4") (pinfunction "ON/OFF_4") (pintype "input"))
    )
    (net (code "62") (name "Net-(U1-OUTPUT)") (class "Default")
      (node (ref "D2") (pin "2") (pinfunction "2_2") (pintype "input"))
      (node (ref "L1") (pin "2") (pinfunction "2_2") (pintype "unspecified"))
      (node (ref "U1") (pin "2") (pinfunction "OUTPUT_2") (pintype "input"))
    )
    (net (code "63") (name "Net-(U7-UD+)") (class "Default")
      (node (ref "U7") (pin "5") (pinfunction "UD+_5") (pintype "unspecified"))
      (node (ref "U8") (pin "6") (pinfunction "6_6") (pintype "unspecified"))
    )
    (net (code "64") (name "Net-(U7-UD-)") (class "Default")
      (node (ref "U7") (pin "6") (pinfunction "UD-_6") (pintype "unspecified"))
      (node (ref "U8") (pin "4") (pinfunction "4_4") (pintype "unspecified"))
    )
    (net (code "65") (name "Net-(U7-V3)") (class "Default")
      (node (ref "C17") (pin "1") (pinfunction "1_1") (pintype "unspecified"))
      (node (ref "U7") (pin "4") (pinfunction "V3_4") (pintype "unspecified"))
    )
    (net (code "66") (name "Net-(U7-XI)") (class "Default")
      (node (ref "C18") (pin "1") (pinfunction "1_1") (pintype "unspecified"))
      (node (ref "U7") (pin "7") (pinfunction "XI_7") (pintype "unspecified"))
      (node (ref "Y1") (pin "2") (pinfunction "OSC2_2") (pintype "unspecified"))
    )
    (net (code "67") (name "Net-(U7-XO)") (class "Default")
      (node (ref "C19") (pin "1") (pinfunction "1_1") (pintype "unspecified"))
      (node (ref "U7") (pin "8") (pinfunction "XO_8") (pintype "unspecified"))
      (node (ref "Y1") (pin "1") (pinfunction "OSC1_1") (pintype "unspecified"))
    )
    (net (code "68") (name "VIN_24V") (class "Default")
      (node (ref "C2") (pin "1") (pintype "unspecified"))
      (node (ref "C3") (pin "2") (pinfunction "2_2") (pintype "unspecified"))
      (node (ref "D1") (pin "2") (pinfunction "2_2") (pintype "unspecified"))
      (node (ref "U1") (pin "1") (pinfunction "VIN_1") (pintype "input"))
    )
    (net (code "69") (name "VUSB") (class "Default")
      (node (ref "D9") (pin "2") (pinfunction "A_2") (pintype "input"))
      (node (ref "P12") (pin "1") (pinfunction "VBUS_1") (pintype "unspecified"))
      (node (ref "U8") (pin "5") (pinfunction "5_5") (pintype "unspecified"))
    )
    (net (code "70") (name "unconnected-(R19-Pad2)") (class "Default")
      (node (ref "R19") (pin "2") (pinfunction "2_2") (pintype "input"))
    )
    (net (code "71") (name "unconnected-(U4-NC-Pad1)") (class "Default")
      (node (ref "U4") (pin "1") (pinfunction "NC_1") (pintype "unspecified"))
    )
    (net (code "72") (name "unconnected-(U5-CLK-Pad20)") (class "Default")
      (node (ref "U5") (pin "20") (pinfunction "CLK_20") (pintype "unspecified"))
    )
    (net (code "73") (name "unconnected-(U5-CMD-Pad19)") (class "Default")
      (node (ref "U5") (pin "19") (pinfunction "CMD_19") (pintype "unspecified"))
    )
    (net (code "74") (name "unconnected-(U5-NC-Pad32)") (class "Default")
      (node (ref "U5") (pin "32") (pinfunction "NC_32") (pintype "unspecified"))
    )
    (net (code "75") (name "unconnected-(U5-SD0-Pad21)") (class "Default")
      (node (ref "U5") (pin "21") (pinfunction "SD0_21") (pintype "unspecified"))
    )
    (net (code "76") (name "unconnected-(U5-SD1-Pad22)") (class "Default")
      (node (ref "U5") (pin "22") (pinfunction "SD1_22") (pintype "unspecified"))
    )
    (net (code "77") (name "unconnected-(U5-SD2-Pad17)") (class "Default")
      (node (ref "U5") (pin "17") (pinfunction "SD2_17") (pintype "unspecified"))
    )
    (net (code "78") (name "unconnected-(U5-SD3-Pad18)") (class "Default")
      (node (ref "U5") (pin "18") (pinfunction "SD3_18") (pintype "unspecified"))
    )
    (net (code "79") (name "unconnected-(U6-NC-Pad1)") (class "Default")
      (node (ref "U6") (pin "1") (pinfunction "NC_1") (pintype "unspecified"))
    )
    (net (code "80") (name "unconnected-(U7-CTS#-Pad9)") (class "Default")
      (node (ref "U7") (pin "9") (pinfunction "CTS#_9") (pintype "unspecified"))
    )
    (net (code "81") (name "unconnected-(U7-DCD#-Pad12)") (class "Default")
      (node (ref "U7") (pin "12") (pinfunction "DCD#_12") (pintype "unspecified"))
    )
    (net (code "82") (name "unconnected-(U7-DSR#-Pad10)") (class "Default")
      (node (ref "U7") (pin "10") (pinfunction "DSR#_10") (pintype "unspecified"))
    )
    (net (code "83") (name "unconnected-(U7-R232-Pad15)") (class "Default")
      (node (ref "U7") (pin "15") (pinfunction "R232_15") (pintype "unspecified"))
    )
    (net (code "84") (name "unconnected-(U7-RI#-Pad11)") (class "Default")
      (node (ref "U7") (pin "11") (pinfunction "RI#_11") (pintype "unspecified"))
    )
  )
)
